# REV_A.net
KiCad netlist of a schematic drawn in EAGLE
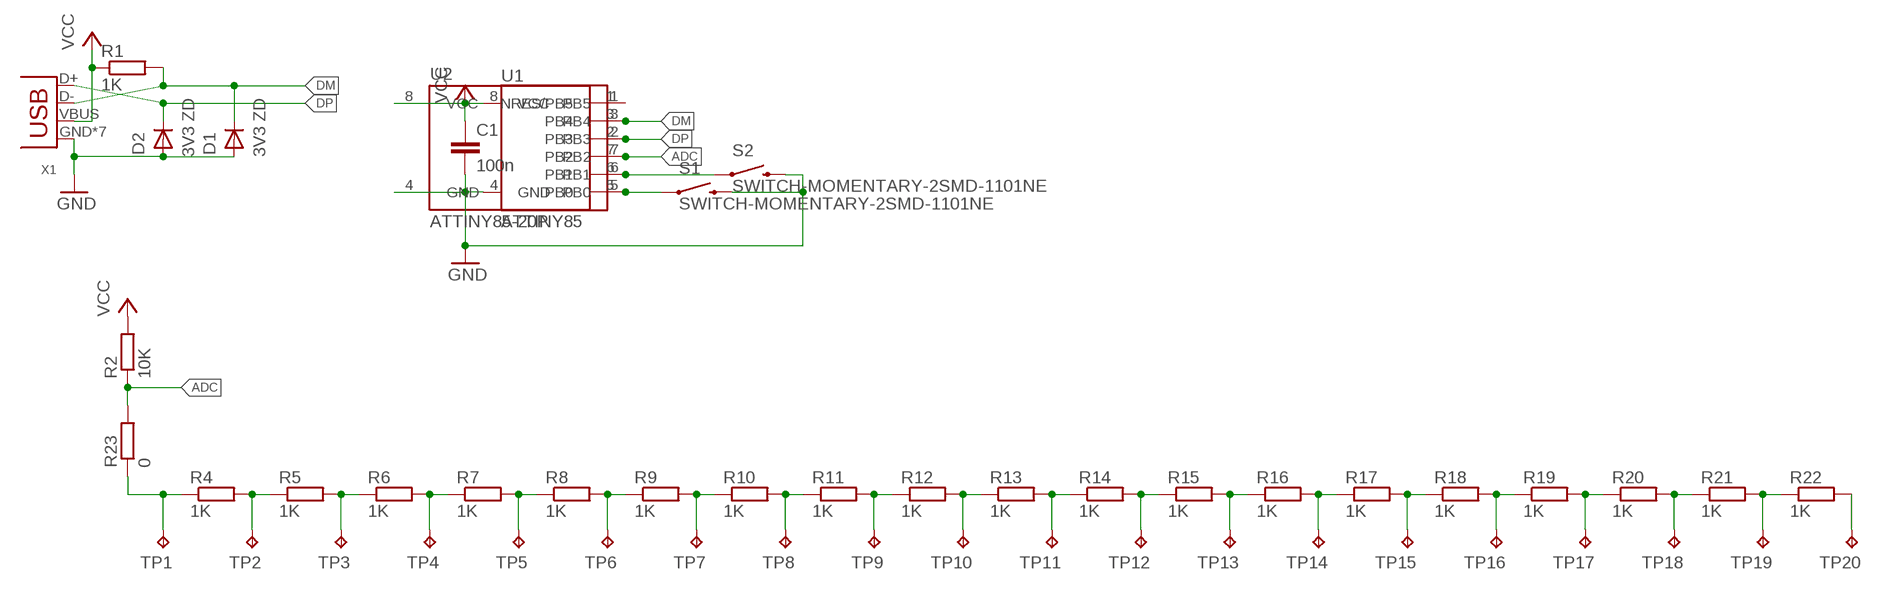
[diagram p0: schematic, sheet 1]

(export (version "E")
  (design (tool "Eeschema 10.0.6"))
  (components
    (comp (ref "C1")
      (value "100n")
      (footprint "eagle-import:C0805K")
      (libsource (lib "eagle-import") (part "C-EUC0805K"))
    )
    (comp (ref "D1")
      (value "3V3 ZD")
      (footprint "eagle-import:SOD80C")
      (libsource (lib "eagle-import") (part "BAS32L"))
    )
    (comp (ref "D2")
      (value "3V3 ZD")
      (footprint "eagle-import:SOD80C")
      (libsource (lib "eagle-import") (part "BAS32L"))
    )
    (comp (ref "R1")
      (value "1K")
      (footprint "eagle-import:M0805")
      (libsource (lib "eagle-import") (part "R-EU_M0805"))
    )
    (comp (ref "R2")
      (value "10K")
      (footprint "eagle-import:M0805")
      (libsource (lib "eagle-import") (part "R-EU_M0805"))
    )
    (comp (ref "R4")
      (value "1K")
      (footprint "eagle-import:M0805")
      (libsource (lib "eagle-import") (part "R-EU_M0805"))
    )
    (comp (ref "R5")
      (value "1K")
      (footprint "eagle-import:M0805")
      (libsource (lib "eagle-import") (part "R-EU_M0805"))
    )
    (comp (ref "R6")
      (value "1K")
      (footprint "eagle-import:M0805")
      (libsource (lib "eagle-import") (part "R-EU_M0805"))
    )
    (comp (ref "R7")
      (value "1K")
      (footprint "eagle-import:M0805")
      (libsource (lib "eagle-import") (part "R-EU_M0805"))
    )
    (comp (ref "R8")
      (value "1K")
      (footprint "eagle-import:M0805")
      (libsource (lib "eagle-import") (part "R-EU_M0805"))
    )
    (comp (ref "R9")
      (value "1K")
      (footprint "eagle-import:M0805")
      (libsource (lib "eagle-import") (part "R-EU_M0805"))
    )
    (comp (ref "R10")
      (value "1K")
      (footprint "eagle-import:M0805")
      (libsource (lib "eagle-import") (part "R-EU_M0805"))
    )
    (comp (ref "R11")
      (value "1K")
      (footprint "eagle-import:M0805")
      (libsource (lib "eagle-import") (part "R-EU_M0805"))
    )
    (comp (ref "R12")
      (value "1K")
      (footprint "eagle-import:M0805")
      (libsource (lib "eagle-import") (part "R-EU_M0805"))
    )
    (comp (ref "R13")
      (value "1K")
      (footprint "eagle-import:M0805")
      (libsource (lib "eagle-import") (part "R-EU_M0805"))
    )
    (comp (ref "R14")
      (value "1K")
      (footprint "eagle-import:M0805")
      (libsource (lib "eagle-import") (part "R-EU_M0805"))
    )
    (comp (ref "R15")
      (value "1K")
      (footprint "eagle-import:M0805")
      (libsource (lib "eagle-import") (part "R-EU_M0805"))
    )
    (comp (ref "R16")
      (value "1K")
      (footprint "eagle-import:M0805")
      (libsource (lib "eagle-import") (part "R-EU_M0805"))
    )
    (comp (ref "R17")
      (value "1K")
      (footprint "eagle-import:M0805")
      (libsource (lib "eagle-import") (part "R-EU_M0805"))
    )
    (comp (ref "R18")
      (value "1K")
      (footprint "eagle-import:M0805")
      (libsource (lib "eagle-import") (part "R-EU_M0805"))
    )
    (comp (ref "R19")
      (value "1K")
      (footprint "eagle-import:M0805")
      (libsource (lib "eagle-import") (part "R-EU_M0805"))
    )
    (comp (ref "R20")
      (value "1K")
      (footprint "eagle-import:M0805")
      (libsource (lib "eagle-import") (part "R-EU_M0805"))
    )
    (comp (ref "R21")
      (value "1K")
      (footprint "eagle-import:M0805")
      (libsource (lib "eagle-import") (part "R-EU_M0805"))
    )
    (comp (ref "R22")
      (value "1K")
      (footprint "eagle-import:M0805")
      (libsource (lib "eagle-import") (part "R-EU_M0805"))
    )
    (comp (ref "R23")
      (value "0")
      (footprint "eagle-import:M1206")
      (libsource (lib "eagle-import") (part "R-EU_M1206"))
    )
    (comp (ref "S1")
      (value "SWITCH-MOMENTARY-2SMD-1101NE")
      (footprint "eagle-import:TACTILE-SWITCH-1101NE")
      (libsource (lib "eagle-import") (part "SWITCH-MOMENTARY-2SMD-1101NE"))
    )
    (comp (ref "S2")
      (value "SWITCH-MOMENTARY-2SMD-1101NE")
      (footprint "eagle-import:TACTILE-SWITCH-1101NE")
      (libsource (lib "eagle-import") (part "SWITCH-MOMENTARY-2SMD-1101NE"))
    )
    (comp (ref "TP1")
      (value "TPB1,27")
      (footprint "eagle-import:B1,27")
      (libsource (lib "eagle-import") (part "TPB1,27"))
    )
    (comp (ref "TP2")
      (value "TPB1,27")
      (footprint "eagle-import:B1,27")
      (libsource (lib "eagle-import") (part "TPB1,27"))
    )
    (comp (ref "TP3")
      (value "TPB1,27")
      (footprint "eagle-import:B1,27")
      (libsource (lib "eagle-import") (part "TPB1,27"))
    )
    (comp (ref "TP4")
      (value "TPB1,27")
      (footprint "eagle-import:B1,27")
      (libsource (lib "eagle-import") (part "TPB1,27"))
    )
    (comp (ref "TP5")
      (value "TPB1,27")
      (footprint "eagle-import:B1,27")
      (libsource (lib "eagle-import") (part "TPB1,27"))
    )
    (comp (ref "TP6")
      (value "TPB1,27")
      (footprint "eagle-import:B1,27")
      (libsource (lib "eagle-import") (part "TPB1,27"))
    )
    (comp (ref "TP7")
      (value "TPB1,27")
      (footprint "eagle-import:B1,27")
      (libsource (lib "eagle-import") (part "TPB1,27"))
    )
    (comp (ref "TP8")
      (value "TPB1,27")
      (footprint "eagle-import:B1,27")
      (libsource (lib "eagle-import") (part "TPB1,27"))
    )
    (comp (ref "TP9")
      (value "TPB1,27")
      (footprint "eagle-import:B1,27")
      (libsource (lib "eagle-import") (part "TPB1,27"))
    )
    (comp (ref "TP10")
      (value "TPB1,27")
      (footprint "eagle-import:B1,27")
      (libsource (lib "eagle-import") (part "TPB1,27"))
    )
    (comp (ref "TP11")
      (value "TPB1,27")
      (footprint "eagle-import:B1,27")
      (libsource (lib "eagle-import") (part "TPB1,27"))
    )
    (comp (ref "TP12")
      (value "TPB1,27")
      (footprint "eagle-import:B1,27")
      (libsource (lib "eagle-import") (part "TPB1,27"))
    )
    (comp (ref "TP13")
      (value "TPB1,27")
      (footprint "eagle-import:B1,27")
      (libsource (lib "eagle-import") (part "TPB1,27"))
    )
    (comp (ref "TP14")
      (value "TPB1,27")
      (footprint "eagle-import:B1,27")
      (libsource (lib "eagle-import") (part "TPB1,27"))
    )
    (comp (ref "TP15")
      (value "TPB1,27")
      (footprint "eagle-import:B1,27")
      (libsource (lib "eagle-import") (part "TPB1,27"))
    )
    (comp (ref "TP16")
      (value "TPB1,27")
      (footprint "eagle-import:B1,27")
      (libsource (lib "eagle-import") (part "TPB1,27"))
    )
    (comp (ref "TP17")
      (value "TPB1,27")
      (footprint "eagle-import:B1,27")
      (libsource (lib "eagle-import") (part "TPB1,27"))
    )
    (comp (ref "TP18")
      (value "TPB1,27")
      (footprint "eagle-import:B1,27")
      (libsource (lib "eagle-import") (part "TPB1,27"))
    )
    (comp (ref "TP19")
      (value "TPB1,27")
      (footprint "eagle-import:B1,27")
      (libsource (lib "eagle-import") (part "TPB1,27"))
    )
    (comp (ref "TP20")
      (value "TPB1,27")
      (footprint "eagle-import:B1,27")
      (libsource (lib "eagle-import") (part "TPB1,27"))
    )
    (comp (ref "U1")
      (value "ATTINY85")
      (footprint "eagle-import:ATTINY85")
      (libsource (lib "eagle-import") (part "ATTINY85"))
    )
    (comp (ref "U2")
      (value "ATTINY85-20P")
      (footprint "eagle-import:PDIP08_300MIL")
      (libsource (lib "eagle-import") (part "ATTINY85P-20"))
    )
    (comp (ref "X1")
      (value "USB-MB-S")
      (footprint "eagle-import:USB-MB-S")
      (libsource (lib "eagle-import") (part "USB-MB-S"))
    )
  )
  (nets
    (net (code "1") (name "ADC") (class "Default")
      (node (ref "R2") (pin "1") (pinfunction "1_1") (pintype "passive"))
      (node (ref "R23") (pin "2") (pinfunction "2_2") (pintype "passive"))
      (node (ref "U1") (pin "7") (pinfunction "PB2_7") (pintype "bidirectional"))
      (node (ref "U2") (pin "7") (pinfunction "PB2_7") (pintype "bidirectional"))
    )
    (net (code "2") (name "DM") (class "Default")
      (node (ref "D1") (pin "1") (pinfunction "K_1") (pintype "passive"))
      (node (ref "R1") (pin "2") (pinfunction "2_2") (pintype "passive"))
      (node (ref "U1") (pin "3") (pinfunction "PB4_3") (pintype "bidirectional"))
      (node (ref "U2") (pin "3") (pinfunction "PB4_3") (pintype "bidirectional"))
      (node (ref "X1") (pin "D-") (pinfunction "D-_D-") (pintype "bidirectional"))
    )
    (net (code "3") (name "DP") (class "Default")
      (node (ref "D2") (pin "1") (pinfunction "K_1") (pintype "passive"))
      (node (ref "U1") (pin "2") (pinfunction "PB3_2") (pintype "bidirectional"))
      (node (ref "U2") (pin "2") (pinfunction "PB3_2") (pintype "bidirectional"))
      (node (ref "X1") (pin "D+") (pinfunction "D+_D+") (pintype "bidirectional"))
    )
    (net (code "4") (name "GND") (class "Default")
      (node (ref "C1") (pin "2") (pinfunction "2_2") (pintype "passive"))
      (node (ref "D1") (pin "2") (pinfunction "A_2") (pintype "passive"))
      (node (ref "D2") (pin "2") (pinfunction "A_2") (pintype "passive"))
      (node (ref "S1") (pin "2") (pinfunction "2_2") (pintype "passive"))
      (node (ref "S2") (pin "2") (pinfunction "2_2") (pintype "passive"))
      (node (ref "U1") (pin "4") (pinfunction "GND_4") (pintype "bidirectional"))
      (node (ref "U2") (pin "4") (pinfunction "GND_4") (pintype "power_in"))
      (node (ref "X1") (pin "GND") (pinfunction "GND_GND") (pintype "bidirectional"))
      (node (ref "X1") (pin "P$1") (pinfunction "GND_P$1") (pintype "bidirectional"))
      (node (ref "X1") (pin "P$2") (pinfunction "GND_P$2") (pintype "bidirectional"))
      (node (ref "X1") (pin "P$3") (pinfunction "GND_P$3") (pintype "bidirectional"))
      (node (ref "X1") (pin "P$4") (pinfunction "GND_P$4") (pintype "bidirectional"))
      (node (ref "X1") (pin "P$5") (pinfunction "GND_P$5") (pintype "bidirectional"))
      (node (ref "X1") (pin "P$6") (pinfunction "GND_P$6") (pintype "bidirectional"))
    )
    (net (code "5") (name "Net-(R4-Pad2)") (class "Default")
      (node (ref "R4") (pin "2") (pinfunction "2_2") (pintype "passive"))
      (node (ref "R5") (pin "1") (pinfunction "1_1") (pintype "passive"))
      (node (ref "TP2") (pin "TP") (pinfunction "TP_TP") (pintype "input"))
    )
    (net (code "6") (name "Net-(R5-Pad2)") (class "Default")
      (node (ref "R5") (pin "2") (pinfunction "2_2") (pintype "passive"))
      (node (ref "R6") (pin "1") (pinfunction "1_1") (pintype "passive"))
      (node (ref "TP3") (pin "TP") (pinfunction "TP_TP") (pintype "input"))
    )
    (net (code "7") (name "Net-(R6-Pad2)") (class "Default")
      (node (ref "R6") (pin "2") (pinfunction "2_2") (pintype "passive"))
      (node (ref "R7") (pin "1") (pinfunction "1_1") (pintype "passive"))
      (node (ref "TP4") (pin "TP") (pinfunction "TP_TP") (pintype "input"))
    )
    (net (code "8") (name "Net-(R7-Pad2)") (class "Default")
      (node (ref "R7") (pin "2") (pinfunction "2_2") (pintype "passive"))
      (node (ref "R8") (pin "1") (pinfunction "1_1") (pintype "passive"))
      (node (ref "TP5") (pin "TP") (pinfunction "TP_TP") (pintype "input"))
    )
    (net (code "9") (name "Net-(R8-Pad2)") (class "Default")
      (node (ref "R8") (pin "2") (pinfunction "2_2") (pintype "passive"))
      (node (ref "R9") (pin "1") (pinfunction "1_1") (pintype "passive"))
      (node (ref "TP6") (pin "TP") (pinfunction "TP_TP") (pintype "input"))
    )
    (net (code "10") (name "Net-(R10-Pad1)") (class "Default")
      (node (ref "R10") (pin "1") (pinfunction "1_1") (pintype "passive"))
      (node (ref "R9") (pin "2") (pinfunction "2_2") (pintype "passive"))
      (node (ref "TP7") (pin "TP") (pinfunction "TP_TP") (pintype "input"))
    )
    (net (code "11") (name "Net-(R10-Pad2)") (class "Default")
      (node (ref "R10") (pin "2") (pinfunction "2_2") (pintype "passive"))
      (node (ref "R11") (pin "1") (pinfunction "1_1") (pintype "passive"))
      (node (ref "TP8") (pin "TP") (pinfunction "TP_TP") (pintype "input"))
    )
    (net (code "12") (name "Net-(R11-Pad2)") (class "Default")
      (node (ref "R11") (pin "2") (pinfunction "2_2") (pintype "passive"))
      (node (ref "R12") (pin "1") (pinfunction "1_1") (pintype "passive"))
      (node (ref "TP9") (pin "TP") (pinfunction "TP_TP") (pintype "input"))
    )
    (net (code "13") (name "Net-(R12-Pad2)") (class "Default")
      (node (ref "R12") (pin "2") (pinfunction "2_2") (pintype "passive"))
      (node (ref "R13") (pin "1") (pinfunction "1_1") (pintype "passive"))
      (node (ref "TP10") (pin "TP") (pinfunction "TP_TP") (pintype "input"))
    )
    (net (code "14") (name "Net-(R13-Pad2)") (class "Default")
      (node (ref "R13") (pin "2") (pinfunction "2_2") (pintype "passive"))
      (node (ref "R14") (pin "1") (pinfunction "1_1") (pintype "passive"))
      (node (ref "TP11") (pin "TP") (pinfunction "TP_TP") (pintype "input"))
    )
    (net (code "15") (name "Net-(R14-Pad2)") (class "Default")
      (node (ref "R14") (pin "2") (pinfunction "2_2") (pintype "passive"))
      (node (ref "R15") (pin "1") (pinfunction "1_1") (pintype "passive"))
      (node (ref "TP12") (pin "TP") (pinfunction "TP_TP") (pintype "input"))
    )
    (net (code "16") (name "Net-(R15-Pad2)") (class "Default")
      (node (ref "R15") (pin "2") (pinfunction "2_2") (pintype "passive"))
      (node (ref "R16") (pin "1") (pinfunction "1_1") (pintype "passive"))
      (node (ref "TP13") (pin "TP") (pinfunction "TP_TP") (pintype "input"))
    )
    (net (code "17") (name "Net-(R16-Pad2)") (class "Default")
      (node (ref "R16") (pin "2") (pinfunction "2_2") (pintype "passive"))
      (node (ref "R17") (pin "1") (pinfunction "1_1") (pintype "passive"))
      (node (ref "TP14") (pin "TP") (pinfunction "TP_TP") (pintype "input"))
    )
    (net (code "18") (name "Net-(R17-Pad2)") (class "Default")
      (node (ref "R17") (pin "2") (pinfunction "2_2") (pintype "passive"))
      (node (ref "R18") (pin "1") (pinfunction "1_1") (pintype "passive"))
      (node (ref "TP15") (pin "TP") (pinfunction "TP_TP") (pintype "input"))
    )
    (net (code "19") (name "Net-(R18-Pad2)") (class "Default")
      (node (ref "R18") (pin "2") (pinfunction "2_2") (pintype "passive"))
      (node (ref "R19") (pin "1") (pinfunction "1_1") (pintype "passive"))
      (node (ref "TP16") (pin "TP") (pinfunction "TP_TP") (pintype "input"))
    )
    (net (code "20") (name "Net-(R19-Pad2)") (class "Default")
      (node (ref "R19") (pin "2") (pinfunction "2_2") (pintype "passive"))
      (node (ref "R20") (pin "1") (pinfunction "1_1") (pintype "passive"))
      (node (ref "TP17") (pin "TP") (pinfunction "TP_TP") (pintype "input"))
    )
    (net (code "21") (name "Net-(R20-Pad2)") (class "Default")
      (node (ref "R20") (pin "2") (pinfunction "2_2") (pintype "passive"))
      (node (ref "R21") (pin "1") (pinfunction "1_1") (pintype "passive"))
      (node (ref "TP18") (pin "TP") (pinfunction "TP_TP") (pintype "input"))
    )
    (net (code "22") (name "Net-(R21-Pad2)") (class "Default")
      (node (ref "R21") (pin "2") (pinfunction "2_2") (pintype "passive"))
      (node (ref "R22") (pin "1") (pinfunction "1_1") (pintype "passive"))
      (node (ref "TP19") (pin "TP") (pinfunction "TP_TP") (pintype "input"))
    )
    (net (code "23") (name "Net-(R22-Pad2)") (class "Default")
      (node (ref "R22") (pin "2") (pinfunction "2_2") (pintype "passive"))
      (node (ref "TP20") (pin "TP") (pinfunction "TP_TP") (pintype "input"))
    )
    (net (code "24") (name "Net-(R23-Pad1)") (class "Default")
      (node (ref "R23") (pin "1") (pinfunction "1_1") (pintype "passive"))
      (node (ref "R4") (pin "1") (pinfunction "1_1") (pintype "passive"))
      (node (ref "TP1") (pin "TP") (pinfunction "TP_TP") (pintype "input"))
    )
    (net (code "25") (name "Net-(U1-PB0)") (class "Default")
      (node (ref "S1") (pin "1") (pinfunction "1_1") (pintype "passive"))
      (node (ref "U1") (pin "5") (pinfunction "PB0_5") (pintype "bidirectional"))
      (node (ref "U2") (pin "5") (pinfunction "PB0_5") (pintype "bidirectional"))
    )
    (net (code "26") (name "Net-(U1-PB1)") (class "Default")
      (node (ref "S2") (pin "1") (pinfunction "1_1") (pintype "passive"))
      (node (ref "U1") (pin "6") (pinfunction "PB1_6") (pintype "bidirectional"))
      (node (ref "U2") (pin "6") (pinfunction "PB1_6") (pintype "bidirectional"))
    )
    (net (code "27") (name "Net-(U1-PB5)") (class "Default")
      (node (ref "U1") (pin "1") (pinfunction "PB5_1") (pintype "bidirectional"))
      (node (ref "U2") (pin "1") (pinfunction "NRES/PB5_1") (pintype "bidirectional"))
    )
    (net (code "28") (name "VCC") (class "Default")
      (node (ref "C1") (pin "1") (pinfunction "1_1") (pintype "passive"))
      (node (ref "R1") (pin "1") (pinfunction "1_1") (pintype "passive"))
      (node (ref "R2") (pin "2") (pinfunction "2_2") (pintype "passive"))
      (node (ref "U1") (pin "8") (pinfunction "VCC_8") (pintype "bidirectional"))
      (node (ref "U2") (pin "8") (pinfunction "VCC_8") (pintype "power_in"))
      (node (ref "X1") (pin "VBUS") (pinfunction "VBUS_VBUS") (pintype "bidirectional"))
    )
  )
)
